# sensors.net
KiCad netlist of a schematic drawn in Altium Designer
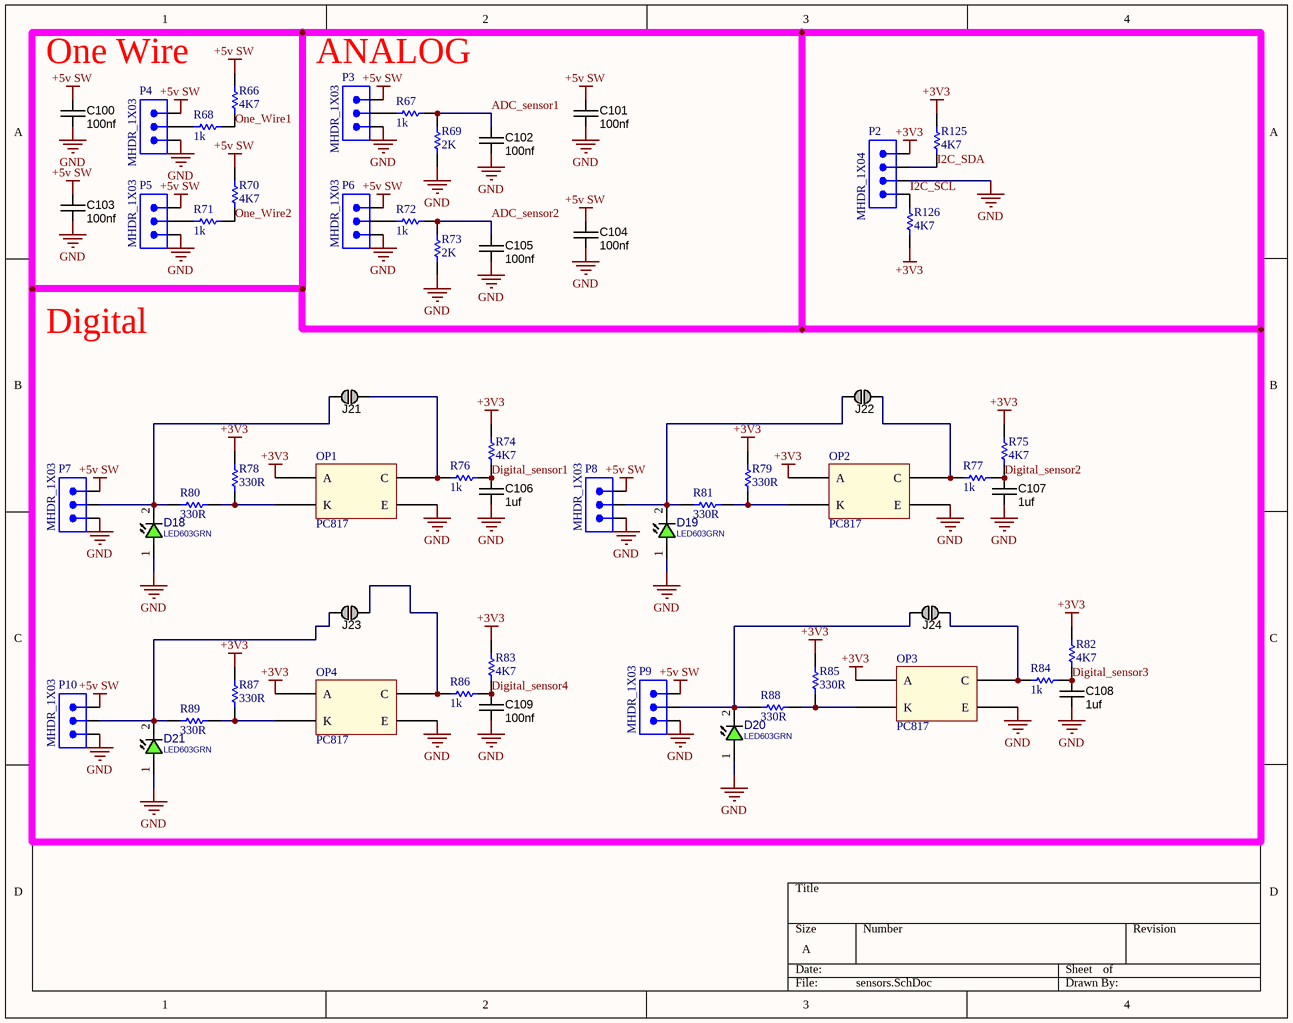
[diagram p0: sensors.SchDoc]

(export (version "E")
  (design (tool "Eeschema 10.0.6"))
  (components
    (comp (ref "C100")
      (value "100nf")
      (footprint "CAPC1608X90N")
      (description "Capacitor SMD Cer 100nF 10% 50V X7R 0603")
      (fields (field (name "TOLERANCE") "±10%"))
      (libsource (lib "altium-import") (part "root_0_CAPC_100n_0603_X7R_50V_10%_"))
    )
    (comp (ref "C101")
      (value "100nf")
      (footprint "CAPC1608X90N")
      (description "Capacitor SMD Cer 100nF 10% 50V X7R 0603")
      (fields (field (name "TOLERANCE") "±10%"))
      (libsource (lib "altium-import") (part "root_0_CAPC_100n_0603_X7R_50V_10%_"))
    )
    (comp (ref "C102")
      (value "100nf")
      (footprint "CAPC1608X90N")
      (description "Capacitor SMD Cer 100nF 10% 50V X7R 0603")
      (fields (field (name "TOLERANCE") "±10%"))
      (libsource (lib "altium-import") (part "root_0_CAPC_100n_0603_X7R_50V_10%_"))
    )
    (comp (ref "C103")
      (value "100nf")
      (footprint "CAPC1608X90N")
      (description "Capacitor SMD Cer 100nF 10% 50V X7R 0603")
      (fields (field (name "TOLERANCE") "±10%"))
      (libsource (lib "altium-import") (part "root_0_CAPC_100n_0603_X7R_50V_10%_"))
    )
    (comp (ref "C104")
      (value "100nf")
      (footprint "CAPC1608X90N")
      (description "Capacitor SMD Cer 100nF 10% 50V X7R 0603")
      (fields (field (name "TOLERANCE") "±10%"))
      (libsource (lib "altium-import") (part "root_0_CAPC_100n_0603_X7R_50V_10%_"))
    )
    (comp (ref "C105")
      (value "100nf")
      (footprint "CAPC1608X90N")
      (description "Capacitor SMD Cer 100nF 10% 50V X7R 0603")
      (fields (field (name "TOLERANCE") "±10%"))
      (libsource (lib "altium-import") (part "root_0_CAPC_100n_0603_X7R_50V_10%_"))
    )
    (comp (ref "C106")
      (value "1uf")
      (footprint "CAPC1608X90N")
      (description "Capacitor SMD Cer 100nF 10% 50V X7R 0603")
      (fields (field (name "TOLERANCE") "±10%"))
      (libsource (lib "altium-import") (part "root_0_CAPC_100n_0603_X7R_50V_10%_"))
    )
    (comp (ref "C107")
      (value "1uf")
      (footprint "CAPC1608X90N")
      (description "Capacitor SMD Cer 100nF 10% 50V X7R 0603")
      (fields (field (name "TOLERANCE") "±10%"))
      (libsource (lib "altium-import") (part "root_0_CAPC_100n_0603_X7R_50V_10%_"))
    )
    (comp (ref "C108")
      (value "1uf")
      (footprint "CAPC1608X90N")
      (description "Capacitor SMD Cer 100nF 10% 50V X7R 0603")
      (fields (field (name "TOLERANCE") "±10%"))
      (libsource (lib "altium-import") (part "root_0_CAPC_100n_0603_X7R_50V_10%_"))
    )
    (comp (ref "C109")
      (value "100nf")
      (footprint "CAPC1608X90N")
      (description "Capacitor SMD Cer 100nF 10% 50V X7R 0603")
      (fields (field (name "TOLERANCE") "±10%"))
      (libsource (lib "altium-import") (part "root_0_CAPC_100n_0603_X7R_50V_10%_"))
    )
    (comp (ref "D18")
      (value "LED603GRN")
      (footprint "LED0603GRN")
      (description "LED, SMD, 0603, GREEN")
      (fields (field (name "MANF") "Kingbright") (field (name "MANF_P#") "APT1608SGC"))
      (libsource (lib "led(diode)") (part "LED_SMD_0603_GRN"))
    )
    (comp (ref "D19")
      (value "LED603GRN")
      (footprint "LED0603GRN")
      (description "LED, SMD, 0603, GREEN")
      (fields (field (name "MANF") "Kingbright") (field (name "MANF_P#") "APT1608SGC"))
      (libsource (lib "led(diode)") (part "LED_SMD_0603_GRN"))
    )
    (comp (ref "D20")
      (value "LED603GRN")
      (footprint "LED0603GRN")
      (description "LED, SMD, 0603, GREEN")
      (fields (field (name "MANF") "Kingbright") (field (name "MANF_P#") "APT1608SGC"))
      (libsource (lib "led(diode)") (part "LED_SMD_0603_GRN"))
    )
    (comp (ref "D21")
      (value "LED603GRN")
      (footprint "LED0603GRN")
      (description "LED, SMD, 0603, GREEN")
      (fields (field (name "MANF") "Kingbright") (field (name "MANF_P#") "APT1608SGC"))
      (libsource (lib "led(diode)") (part "LED_SMD_0603_GRN"))
    )
    (comp (ref "J21")
      (value "Jumper")
      (footprint "JUMP1")
      (description "SMD jumper")
      (libsource (lib "Utiliti_Library") (part "JUMP1"))
    )
    (comp (ref "J22")
      (value "Jumper")
      (footprint "JUMP1")
      (description "SMD jumper")
      (libsource (lib "Utiliti_Library") (part "JUMP1"))
    )
    (comp (ref "J23")
      (value "Jumper")
      (footprint "JUMP1")
      (description "SMD jumper")
      (libsource (lib "Utiliti_Library") (part "JUMP1"))
    )
    (comp (ref "J24")
      (value "Jumper")
      (footprint "JUMP1")
      (description "SMD jumper")
      (libsource (lib "Utiliti_Library") (part "JUMP1"))
    )
    (comp (ref "OP1")
      (value "PC817")
      (footprint "PC817 SMD")
      (description "PC817 optocpler")
      (libsource (lib "IC") (part "PC817"))
    )
    (comp (ref "OP2")
      (value "PC817")
      (footprint "PC817 SMD")
      (description "PC817 optocpler")
      (libsource (lib "IC") (part "PC817"))
    )
    (comp (ref "OP3")
      (value "PC817")
      (footprint "PC817 SMD")
      (description "PC817 optocpler")
      (libsource (lib "IC") (part "PC817"))
    )
    (comp (ref "OP4")
      (value "PC817")
      (footprint "PC817 SMD")
      (description "PC817 optocpler")
      (libsource (lib "IC") (part "PC817"))
    )
    (comp (ref "P2")
      (value "MHDR_1X04")
      (footprint "MHDR1X04-254P")
      (description "Male Header 1X04")
      (libsource (lib "Connector_15 and Sockets") (part "MHDR_1X04"))
    )
    (comp (ref "P3")
      (value "MHDR_1X03")
      (footprint "MHDR1X03-254P")
      (description "Male Header 1X03")
      (libsource (lib "SJ Sockets & Connectors (1)") (part "MHDR_1X03"))
    )
    (comp (ref "P4")
      (value "MHDR_1X03")
      (footprint "MHDR1X03-254P")
      (description "Male Header 1X03")
      (libsource (lib "SJ Sockets & Connectors (1)") (part "MHDR_1X03"))
    )
    (comp (ref "P5")
      (value "MHDR_1X03")
      (footprint "MHDR1X03-254P")
      (description "Male Header 1X03")
      (libsource (lib "SJ Sockets & Connectors (1)") (part "MHDR_1X03"))
    )
    (comp (ref "P6")
      (value "MHDR_1X03")
      (footprint "MHDR1X03-254P")
      (description "Male Header 1X03")
      (libsource (lib "SJ Sockets & Connectors (1)") (part "MHDR_1X03"))
    )
    (comp (ref "P7")
      (value "MHDR_1X03")
      (footprint "MHDR1X03-254P")
      (description "Male Header 1X03")
      (libsource (lib "SJ Sockets & Connectors (1)") (part "MHDR_1X03"))
    )
    (comp (ref "P8")
      (value "MHDR_1X03")
      (footprint "MHDR1X03-254P")
      (description "Male Header 1X03")
      (libsource (lib "SJ Sockets & Connectors (1)") (part "MHDR_1X03"))
    )
    (comp (ref "P9")
      (value "MHDR_1X03")
      (footprint "MHDR1X03-254P")
      (description "Male Header 1X03")
      (libsource (lib "SJ Sockets & Connectors (1)") (part "MHDR_1X03"))
    )
    (comp (ref "P10")
      (value "MHDR_1X03")
      (footprint "MHDR1X03-254P")
      (description "Male Header 1X03")
      (libsource (lib "SJ Sockets & Connectors (1)") (part "MHDR_1X03"))
    )
    (comp (ref "R66")
      (value "4K7")
      (footprint "Resistor_SMD_0603 (1608)")
      (description "Resistor 0603")
      (fields (field (name "PUBLISHER") "Seyed Razi Vesali") (field (name "EMAIL") "razi.vesali@gmail.com"))
      (libsource (lib "resistors") (part "Resistor"))
    )
    (comp (ref "R67")
      (value "1k")
      (footprint "Resistor_SMD_0603 (1608)")
      (description "Resistor 0603")
      (fields (field (name "PUBLISHER") "Seyed Razi Vesali") (field (name "EMAIL") "razi.vesali@gmail.com"))
      (libsource (lib "resistors") (part "Resistor"))
    )
    (comp (ref "R68")
      (value "1k")
      (footprint "Resistor_SMD_0603 (1608)")
      (description "Resistor 0603")
      (fields (field (name "PUBLISHER") "Seyed Razi Vesali") (field (name "EMAIL") "razi.vesali@gmail.com"))
      (libsource (lib "resistors") (part "Resistor"))
    )
    (comp (ref "R69")
      (value "2K")
      (footprint "Resistor_SMD_0603 (1608)")
      (description "Resistor 0603")
      (fields (field (name "PUBLISHER") "Seyed Razi Vesali") (field (name "EMAIL") "razi.vesali@gmail.com"))
      (libsource (lib "resistors") (part "Resistor"))
    )
    (comp (ref "R70")
      (value "4K7")
      (footprint "Resistor_SMD_0603 (1608)")
      (description "Resistor 0603")
      (fields (field (name "PUBLISHER") "Seyed Razi Vesali") (field (name "EMAIL") "razi.vesali@gmail.com"))
      (libsource (lib "resistors") (part "Resistor"))
    )
    (comp (ref "R71")
      (value "1k")
      (footprint "Resistor_SMD_0603 (1608)")
      (description "Resistor 0603")
      (fields (field (name "PUBLISHER") "Seyed Razi Vesali") (field (name "EMAIL") "razi.vesali@gmail.com"))
      (libsource (lib "resistors") (part "Resistor"))
    )
    (comp (ref "R72")
      (value "1k")
      (footprint "Resistor_SMD_0603 (1608)")
      (description "Resistor 0603")
      (fields (field (name "PUBLISHER") "Seyed Razi Vesali") (field (name "EMAIL") "razi.vesali@gmail.com"))
      (libsource (lib "resistors") (part "Resistor"))
    )
    (comp (ref "R73")
      (value "2K")
      (footprint "Resistor_SMD_0603 (1608)")
      (description "Resistor 0603")
      (fields (field (name "PUBLISHER") "Seyed Razi Vesali") (field (name "EMAIL") "razi.vesali@gmail.com"))
      (libsource (lib "resistors") (part "Resistor"))
    )
    (comp (ref "R74")
      (value "4K7")
      (footprint "Resistor_SMD_0603 (1608)")
      (description "Resistor 0603")
      (fields (field (name "PUBLISHER") "Seyed Razi Vesali") (field (name "EMAIL") "razi.vesali@gmail.com"))
      (libsource (lib "resistors") (part "Resistor"))
    )
    (comp (ref "R75")
      (value "4K7")
      (footprint "Resistor_SMD_0603 (1608)")
      (description "Resistor 0603")
      (fields (field (name "PUBLISHER") "Seyed Razi Vesali") (field (name "EMAIL") "razi.vesali@gmail.com"))
      (libsource (lib "resistors") (part "Resistor"))
    )
    (comp (ref "R76")
      (value "1k")
      (footprint "Resistor_SMD_0603 (1608)")
      (description "Resistor 0603")
      (fields (field (name "PUBLISHER") "Seyed Razi Vesali") (field (name "EMAIL") "razi.vesali@gmail.com"))
      (libsource (lib "resistors") (part "Resistor"))
    )
    (comp (ref "R77")
      (value "1k")
      (footprint "Resistor_SMD_0603 (1608)")
      (description "Resistor 0603")
      (fields (field (name "PUBLISHER") "Seyed Razi Vesali") (field (name "EMAIL") "razi.vesali@gmail.com"))
      (libsource (lib "resistors") (part "Resistor"))
    )
    (comp (ref "R78")
      (value "330R")
      (footprint "Resistor_SMD_0603 (1608)")
      (description "Resistor 0603")
      (fields (field (name "PUBLISHER") "Seyed Razi Vesali") (field (name "EMAIL") "razi.vesali@gmail.com"))
      (libsource (lib "resistors") (part "Resistor"))
    )
    (comp (ref "R79")
      (value "330R")
      (footprint "Resistor_SMD_0603 (1608)")
      (description "Resistor 0603")
      (fields (field (name "PUBLISHER") "Seyed Razi Vesali") (field (name "EMAIL") "razi.vesali@gmail.com"))
      (libsource (lib "resistors") (part "Resistor"))
    )
    (comp (ref "R80")
      (value "330R")
      (footprint "Resistor_SMD_0603 (1608)")
      (description "Resistor 0603")
      (fields (field (name "PUBLISHER") "Seyed Razi Vesali") (field (name "EMAIL") "razi.vesali@gmail.com"))
      (libsource (lib "resistors") (part "Resistor"))
    )
    (comp (ref "R81")
      (value "330R")
      (footprint "Resistor_SMD_0603 (1608)")
      (description "Resistor 0603")
      (fields (field (name "PUBLISHER") "Seyed Razi Vesali") (field (name "EMAIL") "razi.vesali@gmail.com"))
      (libsource (lib "resistors") (part "Resistor"))
    )
    (comp (ref "R82")
      (value "4K7")
      (footprint "Resistor_SMD_0603 (1608)")
      (description "Resistor 0603")
      (fields (field (name "PUBLISHER") "Seyed Razi Vesali") (field (name "EMAIL") "razi.vesali@gmail.com"))
      (libsource (lib "resistors") (part "Resistor"))
    )
    (comp (ref "R83")
      (value "4K7")
      (footprint "Resistor_SMD_0603 (1608)")
      (description "Resistor 0603")
      (fields (field (name "PUBLISHER") "Seyed Razi Vesali") (field (name "EMAIL") "razi.vesali@gmail.com"))
      (libsource (lib "resistors") (part "Resistor"))
    )
    (comp (ref "R84")
      (value "1k")
      (footprint "Resistor_SMD_0603 (1608)")
      (description "Resistor 0603")
      (fields (field (name "PUBLISHER") "Seyed Razi Vesali") (field (name "EMAIL") "razi.vesali@gmail.com"))
      (libsource (lib "resistors") (part "Resistor"))
    )
    (comp (ref "R85")
      (value "330R")
      (footprint "Resistor_SMD_0603 (1608)")
      (description "Resistor 0603")
      (fields (field (name "PUBLISHER") "Seyed Razi Vesali") (field (name "EMAIL") "razi.vesali@gmail.com"))
      (libsource (lib "resistors") (part "Resistor"))
    )
    (comp (ref "R86")
      (value "1k")
      (footprint "Resistor_SMD_0603 (1608)")
      (description "Resistor 0603")
      (fields (field (name "PUBLISHER") "Seyed Razi Vesali") (field (name "EMAIL") "razi.vesali@gmail.com"))
      (libsource (lib "resistors") (part "Resistor"))
    )
    (comp (ref "R87")
      (value "330R")
      (footprint "Resistor_SMD_0603 (1608)")
      (description "Resistor 0603")
      (fields (field (name "PUBLISHER") "Seyed Razi Vesali") (field (name "EMAIL") "razi.vesali@gmail.com"))
      (libsource (lib "resistors") (part "Resistor"))
    )
    (comp (ref "R88")
      (value "330R")
      (footprint "Resistor_SMD_0603 (1608)")
      (description "Resistor 0603")
      (fields (field (name "PUBLISHER") "Seyed Razi Vesali") (field (name "EMAIL") "razi.vesali@gmail.com"))
      (libsource (lib "resistors") (part "Resistor"))
    )
    (comp (ref "R89")
      (value "330R")
      (footprint "Resistor_SMD_0603 (1608)")
      (description "Resistor 0603")
      (fields (field (name "PUBLISHER") "Seyed Razi Vesali") (field (name "EMAIL") "razi.vesali@gmail.com"))
      (libsource (lib "resistors") (part "Resistor"))
    )
    (comp (ref "R125")
      (value "4K7")
      (footprint "Resistor_SMD_0603 (1608)")
      (description "Resistor 0603")
      (fields (field (name "PUBLISHER") "Seyed Razi Vesali") (field (name "EMAIL") "razi.vesali@gmail.com"))
      (libsource (lib "resistors") (part "Resistor"))
    )
    (comp (ref "R126")
      (value "4K7")
      (footprint "Resistor_SMD_0603 (1608)")
      (description "Resistor 0603")
      (fields (field (name "PUBLISHER") "Seyed Razi Vesali") (field (name "EMAIL") "razi.vesali@gmail.com"))
      (libsource (lib "resistors") (part "Resistor"))
    )
  )
  (nets
    (net (code "1") (name "+3V3") (class "Default")
      (node (ref "OP1") (pin "1") (pinfunction "A_1") (pintype "passive"))
      (node (ref "OP2") (pin "1") (pinfunction "A_1") (pintype "passive"))
      (node (ref "OP3") (pin "1") (pinfunction "A_1") (pintype "passive"))
      (node (ref "OP4") (pin "1") (pinfunction "A_1") (pintype "passive"))
      (node (ref "P2") (pin "4") (pinfunction "4_4") (pintype "passive"))
      (node (ref "R125") (pin "2") (pinfunction "2_2") (pintype "passive"))
      (node (ref "R126") (pin "2") (pinfunction "2_2") (pintype "passive"))
      (node (ref "R74") (pin "1") (pinfunction "1_1") (pintype "passive"))
      (node (ref "R75") (pin "1") (pinfunction "1_1") (pintype "passive"))
      (node (ref "R78") (pin "1") (pinfunction "1_1") (pintype "passive"))
      (node (ref "R79") (pin "1") (pinfunction "1_1") (pintype "passive"))
      (node (ref "R82") (pin "1") (pinfunction "1_1") (pintype "passive"))
      (node (ref "R83") (pin "1") (pinfunction "1_1") (pintype "passive"))
      (node (ref "R85") (pin "1") (pinfunction "1_1") (pintype "passive"))
      (node (ref "R87") (pin "1") (pinfunction "1_1") (pintype "passive"))
    )
    (net (code "2") (name "+5v SW") (class "Default")
      (node (ref "C100") (pin "1") (pintype "passive"))
      (node (ref "C101") (pin "1") (pintype "passive"))
      (node (ref "C103") (pin "1") (pintype "passive"))
      (node (ref "C104") (pin "1") (pintype "passive"))
      (node (ref "P10") (pin "3") (pinfunction "3_3") (pintype "passive"))
      (node (ref "P3") (pin "3") (pinfunction "3_3") (pintype "passive"))
      (node (ref "P4") (pin "3") (pinfunction "3_3") (pintype "passive"))
      (node (ref "P5") (pin "3") (pinfunction "3_3") (pintype "passive"))
      (node (ref "P6") (pin "3") (pinfunction "3_3") (pintype "passive"))
      (node (ref "P7") (pin "3") (pinfunction "3_3") (pintype "passive"))
      (node (ref "P8") (pin "3") (pinfunction "3_3") (pintype "passive"))
      (node (ref "P9") (pin "3") (pinfunction "3_3") (pintype "passive"))
      (node (ref "R66") (pin "1") (pinfunction "1_1") (pintype "passive"))
      (node (ref "R70") (pin "1") (pinfunction "1_1") (pintype "passive"))
    )
    (net (code "3") (name "/ADC_sensor1") (class "Default")
      (node (ref "C102") (pin "1") (pintype "passive"))
      (node (ref "R67") (pin "1") (pinfunction "1_1") (pintype "passive"))
      (node (ref "R69") (pin "2") (pinfunction "2_2") (pintype "passive"))
    )
    (net (code "4") (name "/ADC_sensor2") (class "Default")
      (node (ref "C105") (pin "1") (pintype "passive"))
      (node (ref "R72") (pin "1") (pinfunction "1_1") (pintype "passive"))
      (node (ref "R73") (pin "2") (pinfunction "2_2") (pintype "passive"))
    )
    (net (code "5") (name "/Digital_sensor1") (class "Default")
      (node (ref "C106") (pin "1") (pintype "passive"))
      (node (ref "R74") (pin "2") (pinfunction "2_2") (pintype "passive"))
      (node (ref "R76") (pin "1") (pinfunction "1_1") (pintype "passive"))
    )
    (net (code "6") (name "/Digital_sensor2") (class "Default")
      (node (ref "C107") (pin "1") (pintype "passive"))
      (node (ref "R75") (pin "2") (pinfunction "2_2") (pintype "passive"))
      (node (ref "R77") (pin "1") (pinfunction "1_1") (pintype "passive"))
    )
    (net (code "7") (name "/Digital_sensor3") (class "Default")
      (node (ref "C108") (pin "1") (pintype "passive"))
      (node (ref "R82") (pin "2") (pinfunction "2_2") (pintype "passive"))
      (node (ref "R84") (pin "1") (pinfunction "1_1") (pintype "passive"))
    )
    (net (code "8") (name "/Digital_sensor4") (class "Default")
      (node (ref "C109") (pin "1") (pintype "passive"))
      (node (ref "R83") (pin "2") (pinfunction "2_2") (pintype "passive"))
      (node (ref "R86") (pin "1") (pinfunction "1_1") (pintype "passive"))
    )
    (net (code "9") (name "/I2C_SCL") (class "Default")
      (node (ref "P2") (pin "1") (pinfunction "1_1") (pintype "passive"))
      (node (ref "R126") (pin "1") (pinfunction "1_1") (pintype "passive"))
    )
    (net (code "10") (name "/I2C_SDA") (class "Default")
      (node (ref "P2") (pin "3") (pinfunction "3_3") (pintype "passive"))
      (node (ref "R125") (pin "1") (pinfunction "1_1") (pintype "passive"))
    )
    (net (code "11") (name "/One_Wire1") (class "Default")
      (node (ref "R66") (pin "2") (pinfunction "2_2") (pintype "passive"))
      (node (ref "R68") (pin "1") (pinfunction "1_1") (pintype "passive"))
    )
    (net (code "12") (name "/One_Wire2") (class "Default")
      (node (ref "R70") (pin "2") (pinfunction "2_2") (pintype "passive"))
      (node (ref "R71") (pin "1") (pinfunction "1_1") (pintype "passive"))
    )
    (net (code "13") (name "GND") (class "Default")
      (node (ref "C100") (pin "2") (pintype "passive"))
      (node (ref "C101") (pin "2") (pintype "passive"))
      (node (ref "C102") (pin "2") (pintype "passive"))
      (node (ref "C103") (pin "2") (pintype "passive"))
      (node (ref "C104") (pin "2") (pintype "passive"))
      (node (ref "C105") (pin "2") (pintype "passive"))
      (node (ref "C106") (pin "2") (pintype "passive"))
      (node (ref "C107") (pin "2") (pintype "passive"))
      (node (ref "C108") (pin "2") (pintype "passive"))
      (node (ref "C109") (pin "2") (pintype "passive"))
      (node (ref "D18") (pin "1") (pinfunction "ANODE_1") (pintype "passive"))
      (node (ref "D19") (pin "1") (pinfunction "ANODE_1") (pintype "passive"))
      (node (ref "D20") (pin "1") (pinfunction "ANODE_1") (pintype "passive"))
      (node (ref "D21") (pin "1") (pinfunction "ANODE_1") (pintype "passive"))
      (node (ref "OP1") (pin "3") (pinfunction "E_3") (pintype "passive"))
      (node (ref "OP2") (pin "3") (pinfunction "E_3") (pintype "passive"))
      (node (ref "OP3") (pin "3") (pinfunction "E_3") (pintype "passive"))
      (node (ref "OP4") (pin "3") (pinfunction "E_3") (pintype "passive"))
      (node (ref "P10") (pin "1") (pinfunction "1_1") (pintype "passive"))
      (node (ref "P2") (pin "2") (pinfunction "2_2") (pintype "passive"))
      (node (ref "P3") (pin "1") (pinfunction "1_1") (pintype "passive"))
      (node (ref "P4") (pin "1") (pinfunction "1_1") (pintype "passive"))
      (node (ref "P5") (pin "1") (pinfunction "1_1") (pintype "passive"))
      (node (ref "P6") (pin "1") (pinfunction "1_1") (pintype "passive"))
      (node (ref "P7") (pin "1") (pinfunction "1_1") (pintype "passive"))
      (node (ref "P8") (pin "1") (pinfunction "1_1") (pintype "passive"))
      (node (ref "P9") (pin "1") (pinfunction "1_1") (pintype "passive"))
      (node (ref "R69") (pin "1") (pinfunction "1_1") (pintype "passive"))
      (node (ref "R73") (pin "1") (pinfunction "1_1") (pintype "passive"))
    )
    (net (code "14") (name "Net-(D18-CATHODE)") (class "Default")
      (node (ref "D18") (pin "2") (pinfunction "CATHODE_2") (pintype "passive"))
      (node (ref "J21") (pin "1") (pintype "passive"))
      (node (ref "P7") (pin "2") (pinfunction "2_2") (pintype "passive"))
      (node (ref "R80") (pin "2") (pinfunction "2_2") (pintype "passive"))
    )
    (net (code "15") (name "Net-(D19-CATHODE)") (class "Default")
      (node (ref "D19") (pin "2") (pinfunction "CATHODE_2") (pintype "passive"))
      (node (ref "J22") (pin "1") (pintype "passive"))
      (node (ref "P8") (pin "2") (pinfunction "2_2") (pintype "passive"))
      (node (ref "R81") (pin "2") (pinfunction "2_2") (pintype "passive"))
    )
    (net (code "16") (name "Net-(D20-CATHODE)") (class "Default")
      (node (ref "D20") (pin "2") (pinfunction "CATHODE_2") (pintype "passive"))
      (node (ref "J24") (pin "1") (pintype "passive"))
      (node (ref "P9") (pin "2") (pinfunction "2_2") (pintype "passive"))
      (node (ref "R88") (pin "2") (pinfunction "2_2") (pintype "passive"))
    )
    (net (code "17") (name "Net-(D21-CATHODE)") (class "Default")
      (node (ref "D21") (pin "2") (pinfunction "CATHODE_2") (pintype "passive"))
      (node (ref "J23") (pin "1") (pintype "passive"))
      (node (ref "P10") (pin "2") (pinfunction "2_2") (pintype "passive"))
      (node (ref "R89") (pin "2") (pinfunction "2_2") (pintype "passive"))
    )
    (net (code "18") (name "Net-(OP1-C)") (class "Default")
      (node (ref "J21") (pin "2") (pintype "passive"))
      (node (ref "OP1") (pin "4") (pinfunction "C_4") (pintype "passive"))
      (node (ref "R76") (pin "2") (pinfunction "2_2") (pintype "passive"))
    )
    (net (code "19") (name "Net-(OP1-K)") (class "Default")
      (node (ref "OP1") (pin "2") (pinfunction "K_2") (pintype "passive"))
      (node (ref "R78") (pin "2") (pinfunction "2_2") (pintype "passive"))
      (node (ref "R80") (pin "1") (pinfunction "1_1") (pintype "passive"))
    )
    (net (code "20") (name "Net-(OP2-C)") (class "Default")
      (node (ref "J22") (pin "2") (pintype "passive"))
      (node (ref "OP2") (pin "4") (pinfunction "C_4") (pintype "passive"))
      (node (ref "R77") (pin "2") (pinfunction "2_2") (pintype "passive"))
    )
    (net (code "21") (name "Net-(OP2-K)") (class "Default")
      (node (ref "OP2") (pin "2") (pinfunction "K_2") (pintype "passive"))
      (node (ref "R79") (pin "2") (pinfunction "2_2") (pintype "passive"))
      (node (ref "R81") (pin "1") (pinfunction "1_1") (pintype "passive"))
    )
    (net (code "22") (name "Net-(OP3-C)") (class "Default")
      (node (ref "J24") (pin "2") (pintype "passive"))
      (node (ref "OP3") (pin "4") (pinfunction "C_4") (pintype "passive"))
      (node (ref "R84") (pin "2") (pinfunction "2_2") (pintype "passive"))
    )
    (net (code "23") (name "Net-(OP3-K)") (class "Default")
      (node (ref "OP3") (pin "2") (pinfunction "K_2") (pintype "passive"))
      (node (ref "R85") (pin "2") (pinfunction "2_2") (pintype "passive"))
      (node (ref "R88") (pin "1") (pinfunction "1_1") (pintype "passive"))
    )
    (net (code "24") (name "Net-(OP4-C)") (class "Default")
      (node (ref "J23") (pin "2") (pintype "passive"))
      (node (ref "OP4") (pin "4") (pinfunction "C_4") (pintype "passive"))
      (node (ref "R86") (pin "2") (pinfunction "2_2") (pintype "passive"))
    )
    (net (code "25") (name "Net-(OP4-K)") (class "Default")
      (node (ref "OP4") (pin "2") (pinfunction "K_2") (pintype "passive"))
      (node (ref "R87") (pin "2") (pinfunction "2_2") (pintype "passive"))
      (node (ref "R89") (pin "1") (pinfunction "1_1") (pintype "passive"))
    )
    (net (code "26") (name "Net-(P3-Pad2)") (class "Default")
      (node (ref "P3") (pin "2") (pinfunction "2_2") (pintype "passive"))
      (node (ref "R67") (pin "2") (pinfunction "2_2") (pintype "passive"))
    )
    (net (code "27") (name "Net-(P4-Pad2)") (class "Default")
      (node (ref "P4") (pin "2") (pinfunction "2_2") (pintype "passive"))
      (node (ref "R68") (pin "2") (pinfunction "2_2") (pintype "passive"))
    )
    (net (code "28") (name "Net-(P5-Pad2)") (class "Default")
      (node (ref "P5") (pin "2") (pinfunction "2_2") (pintype "passive"))
      (node (ref "R71") (pin "2") (pinfunction "2_2") (pintype "passive"))
    )
    (net (code "29") (name "Net-(P6-Pad2)") (class "Default")
      (node (ref "P6") (pin "2") (pinfunction "2_2") (pintype "passive"))
      (node (ref "R72") (pin "2") (pinfunction "2_2") (pintype "passive"))
    )
  )
)
